# partybooth.net
KiCad netlist of a schematic drawn in EAGLE
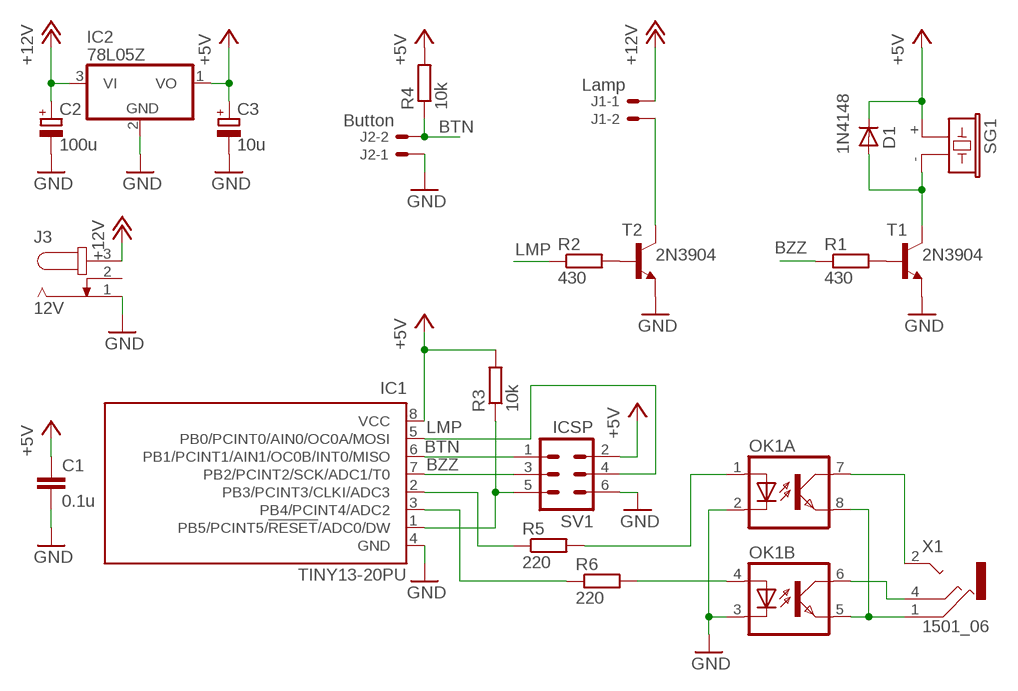
[diagram p0: schematic, sheet 1]

(export (version "E")
  (design (tool "Eeschema 10.0.6"))
  (components
    (comp (ref "C1")
      (value "0.1u")
      (footprint "eagle-import:C050-025X075")
      (libsource (lib "eagle-import") (part "C-EU050-025X075"))
    )
    (comp (ref "C2")
      (value "100u")
      (footprint "eagle-import:E5-6")
      (libsource (lib "eagle-import") (part "CPOL-EUE5-6"))
    )
    (comp (ref "C3")
      (value "10u")
      (footprint "eagle-import:E5-5")
      (libsource (lib "eagle-import") (part "CPOL-EUE5-5"))
    )
    (comp (ref "D1")
      (value "1N4148")
      (footprint "eagle-import:DO35-7")
      (libsource (lib "eagle-import") (part "1N4148DO35-7"))
    )
    (comp (ref "IC1")
      (value "TINY13-20PU")
      (footprint "eagle-import:DIL08")
      (fields (field (name "MPN") "ATTINY13-20PU"))
      (libsource (lib "eagle-import") (part "TINY13PU-20"))
    )
    (comp (ref "IC2")
      (value "78L05Z")
      (footprint "eagle-import:TO92")
      (libsource (lib "eagle-import") (part "78ZL05"))
    )
    (comp (ref "J1")
      (value "Lamp")
      (footprint "eagle-import:6410-02")
      (libsource (lib "eagle-import") (part "22-?-0227-2021"))
    )
    (comp (ref "J2")
      (value "Button")
      (footprint "eagle-import:6410-02")
      (libsource (lib "eagle-import") (part "22-?-0227-2021"))
    )
    (comp (ref "J3")
      (value "12V")
      (footprint "eagle-import:SPC4077")
      (libsource (lib "eagle-import") (part "JACK-PLUG0"))
    )
    (comp (ref "OK1")
      (value "ILD2")
      (footprint "eagle-import:DIL08")
      (libsource (lib "eagle-import") (part "ILD2"))
    )
    (comp (ref "R1")
      (value "430")
      (footprint "eagle-import:0204_7")
      (libsource (lib "eagle-import") (part "R-EU_0204/7"))
    )
    (comp (ref "R2")
      (value "430")
      (footprint "eagle-import:0204_7")
      (libsource (lib "eagle-import") (part "R-EU_0204/7"))
    )
    (comp (ref "R3")
      (value "10k")
      (footprint "eagle-import:0204_7")
      (libsource (lib "eagle-import") (part "R-EU_0204/7"))
    )
    (comp (ref "R4")
      (value "10k")
      (footprint "eagle-import:0204_7")
      (libsource (lib "eagle-import") (part "R-EU_0204/7"))
    )
    (comp (ref "R5")
      (value "220")
      (footprint "eagle-import:0204_7")
      (libsource (lib "eagle-import") (part "R-EU_0204/7"))
    )
    (comp (ref "R6")
      (value "220")
      (footprint "eagle-import:0204_7")
      (libsource (lib "eagle-import") (part "R-EU_0204/7"))
    )
    (comp (ref "SG1")
      (value "F/CM12P")
      (footprint "eagle-import:F_CM12P")
      (libsource (lib "eagle-import") (part "F/CM12P"))
    )
    (comp (ref "SV1")
      (value "ICSP")
      (footprint "eagle-import:MA03-2")
      (libsource (lib "eagle-import") (part "MA03-2"))
    )
    (comp (ref "T1")
      (value "2N3904")
      (footprint "eagle-import:TO92")
      (libsource (lib "eagle-import") (part "2N3904"))
    )
    (comp (ref "T2")
      (value "2N3904")
      (footprint "eagle-import:TO92")
      (libsource (lib "eagle-import") (part "2N3904"))
    )
    (comp (ref "X1")
      (value "1501_06")
      (footprint "eagle-import:1501_06")
      (libsource (lib "eagle-import") (part "1501_06"))
    )
  )
  (nets
    (net (code "1") (name "+5V") (class "Default")
      (node (ref "C1") (pin "1") (pinfunction "1_1") (pintype "passive"))
      (node (ref "C3") (pin "+") (pinfunction "+_+") (pintype "passive"))
      (node (ref "D1") (pin "C") (pinfunction "C_C") (pintype "passive"))
      (node (ref "IC1") (pin "8") (pinfunction "VCC_8") (pintype "power_in"))
      (node (ref "IC2") (pin "1") (pinfunction "VO_1") (pintype "passive"))
      (node (ref "R3") (pin "2") (pinfunction "2_2") (pintype "passive"))
      (node (ref "R4") (pin "2") (pinfunction "2_2") (pintype "passive"))
      (node (ref "SG1") (pin "+") (pinfunction "1_+") (pintype "passive"))
      (node (ref "SV1") (pin "2") (pinfunction "2_2") (pintype "passive"))
    )
    (net (code "2") (name "+12V") (class "Default")
      (node (ref "C2") (pin "+") (pinfunction "+_+") (pintype "passive"))
      (node (ref "IC2") (pin "3") (pinfunction "VI_3") (pintype "input"))
      (node (ref "J1") (pin "1") (pinfunction "S_1") (pintype "passive"))
      (node (ref "J3") (pin "3") (pinfunction "3_3") (pintype "passive"))
    )
    (net (code "3") (name "/BTN") (class "Default")
      (node (ref "IC1") (pin "6") (pinfunction "PB1/PCINT1/AIN1/OC0B/INT0/MISO_6") (pintype "bidirectional"))
      (node (ref "J2") (pin "2") (pinfunction "S_2") (pintype "passive"))
      (node (ref "R4") (pin "1") (pinfunction "1_1") (pintype "passive"))
      (node (ref "SV1") (pin "1") (pinfunction "1_1") (pintype "passive"))
    )
    (net (code "4") (name "/BZZ") (class "Default")
      (node (ref "IC1") (pin "7") (pinfunction "PB2/PCINT2/SCK/ADC1/T0_7") (pintype "bidirectional"))
      (node (ref "R1") (pin "1") (pinfunction "1_1") (pintype "passive"))
      (node (ref "SV1") (pin "3") (pinfunction "3_3") (pintype "passive"))
    )
    (net (code "5") (name "/LMP") (class "Default")
      (node (ref "IC1") (pin "5") (pinfunction "PB0/PCINT0/AIN0/OC0A/MOSI_5") (pintype "bidirectional"))
      (node (ref "R2") (pin "1") (pinfunction "1_1") (pintype "passive"))
      (node (ref "SV1") (pin "4") (pinfunction "4_4") (pintype "passive"))
    )
    (net (code "6") (name "GND") (class "Default")
      (node (ref "C1") (pin "2") (pinfunction "2_2") (pintype "passive"))
      (node (ref "C2") (pin "-") (pinfunction "-_-") (pintype "passive"))
      (node (ref "C3") (pin "-") (pinfunction "-_-") (pintype "passive"))
      (node (ref "IC1") (pin "4") (pinfunction "GND_4") (pintype "power_in"))
      (node (ref "IC2") (pin "2") (pinfunction "GND_2") (pintype "passive"))
      (node (ref "J2") (pin "1") (pinfunction "S_1") (pintype "passive"))
      (node (ref "J3") (pin "1") (pinfunction "1_1") (pintype "passive"))
      (node (ref "OK1") (pin "2") (pinfunction "C_2") (pintype "passive"))
      (node (ref "OK1") (pin "3") (pinfunction "C_3") (pintype "passive"))
      (node (ref "SV1") (pin "6") (pinfunction "6_6") (pintype "passive"))
      (node (ref "T1") (pin "3") (pinfunction "E_3") (pintype "passive"))
      (node (ref "T2") (pin "3") (pinfunction "E_3") (pintype "passive"))
    )
    (net (code "7") (name "Net-(IC1-PB3{slash}PCINT3{slash}CLKI{slash}ADC3)") (class "Default")
      (node (ref "IC1") (pin "2") (pinfunction "PB3/PCINT3/CLKI/ADC3_2") (pintype "bidirectional"))
      (node (ref "R5") (pin "1") (pinfunction "1_1") (pintype "passive"))
    )
    (net (code "8") (name "Net-(IC1-PB4{slash}PCINT4{slash}ADC2)") (class "Default")
      (node (ref "IC1") (pin "3") (pinfunction "PB4/PCINT4/ADC2_3") (pintype "bidirectional"))
      (node (ref "R6") (pin "1") (pinfunction "1_1") (pintype "passive"))
    )
    (net (code "9") (name "Net-(IC1-PB5{slash}PCINT5{slash}~{RESET}{slash}ADC0{slash}DW)") (class "Default")
      (node (ref "IC1") (pin "1") (pinfunction "PB5/PCINT5/~{RESET}/ADC0/DW_1") (pintype "bidirectional"))
      (node (ref "R3") (pin "1") (pinfunction "1_1") (pintype "passive"))
      (node (ref "SV1") (pin "5") (pinfunction "5_5") (pintype "passive"))
    )
    (net (code "10") (name "Net-(J1B-S)") (class "Default")
      (node (ref "J1") (pin "2") (pinfunction "S_2") (pintype "passive"))
      (node (ref "T2") (pin "1") (pinfunction "C_1") (pintype "passive"))
    )
    (net (code "11") (name "Net-(OK1A-A)") (class "Default")
      (node (ref "OK1") (pin "1") (pinfunction "A_1") (pintype "passive"))
      (node (ref "R5") (pin "2") (pinfunction "2_2") (pintype "passive"))
    )
    (net (code "12") (name "Net-(OK1A-COL)") (class "Default")
      (node (ref "OK1") (pin "7") (pinfunction "COL_7") (pintype "passive"))
      (node (ref "X1") (pin "2") (pinfunction "2_2") (pintype "passive"))
    )
    (net (code "13") (name "Net-(OK1A-EMIT)") (class "Default")
      (node (ref "OK1") (pin "5") (pinfunction "EMIT_5") (pintype "passive"))
      (node (ref "OK1") (pin "8") (pinfunction "EMIT_8") (pintype "passive"))
      (node (ref "X1") (pin "1") (pinfunction "1_1") (pintype "passive"))
    )
    (net (code "14") (name "Net-(OK1B-A)") (class "Default")
      (node (ref "OK1") (pin "4") (pinfunction "A_4") (pintype "passive"))
      (node (ref "R6") (pin "2") (pinfunction "2_2") (pintype "passive"))
    )
    (net (code "15") (name "Net-(OK1B-COL)") (class "Default")
      (node (ref "OK1") (pin "6") (pinfunction "COL_6") (pintype "passive"))
      (node (ref "X1") (pin "4") (pinfunction "3_4") (pintype "passive"))
    )
    (net (code "16") (name "Net-(SG1-2)") (class "Default")
      (node (ref "D1") (pin "A") (pinfunction "A_A") (pintype "passive"))
      (node (ref "SG1") (pin "-") (pinfunction "2_-") (pintype "passive"))
      (node (ref "T1") (pin "1") (pinfunction "C_1") (pintype "passive"))
    )
    (net (code "17") (name "Net-(T1-B)") (class "Default")
      (node (ref "R1") (pin "2") (pinfunction "2_2") (pintype "passive"))
      (node (ref "T1") (pin "2") (pinfunction "B_2") (pintype "passive"))
    )
    (net (code "18") (name "Net-(T2-B)") (class "Default")
      (node (ref "R2") (pin "2") (pinfunction "2_2") (pintype "passive"))
      (node (ref "T2") (pin "2") (pinfunction "B_2") (pintype "passive"))
    )
    (net (code "19") (name "unconnected-(J3-Pad2)") (class "Default")
      (node (ref "J3") (pin "2") (pinfunction "2_2") (pintype "passive"))
    )
  )
)
